# SNES-logo-leds.net
KiCad netlist of a schematic drawn in EAGLE
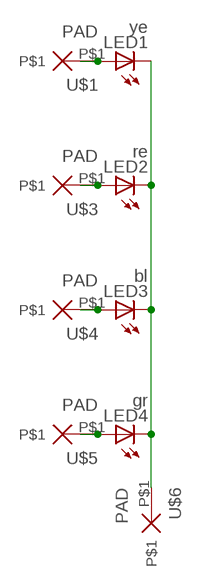
[diagram p0: schematic, sheet 1]

(export (version "E")
  (design (tool "Eeschema 10.0.6"))
  (components
    (comp (ref "LED1")
      (value "ye")
      (footprint "eagle-import:SML0805")
      (libsource (lib "eagle-import") (part "LEDSML0805"))
    )
    (comp (ref "LED2")
      (value "re")
      (footprint "eagle-import:SML0805")
      (libsource (lib "eagle-import") (part "LEDSML0805"))
    )
    (comp (ref "LED3")
      (value "bl")
      (footprint "eagle-import:SML0805")
      (libsource (lib "eagle-import") (part "LEDSML0805"))
    )
    (comp (ref "LED4")
      (value "gr")
      (footprint "eagle-import:SML0805")
      (libsource (lib "eagle-import") (part "LEDSML0805"))
    )
    (comp (ref "U$1")
      (value "PAD")
      (footprint "eagle-import:PAD")
      (libsource (lib "eagle-import") (part "PAD"))
    )
    (comp (ref "U$3")
      (value "PAD")
      (footprint "eagle-import:PAD")
      (libsource (lib "eagle-import") (part "PAD"))
    )
    (comp (ref "U$4")
      (value "PAD")
      (footprint "eagle-import:PAD")
      (libsource (lib "eagle-import") (part "PAD"))
    )
    (comp (ref "U$5")
      (value "PAD")
      (footprint "eagle-import:PAD")
      (libsource (lib "eagle-import") (part "PAD"))
    )
    (comp (ref "U$6")
      (value "PAD")
      (footprint "eagle-import:PAD")
      (libsource (lib "eagle-import") (part "PAD"))
    )
  )
  (nets
    (net (code "1") (name "Net-(LED1-PadA)") (class "Default")
      (node (ref "LED1") (pin "A") (pinfunction "A_A") (pintype "passive"))
      (node (ref "U$1") (pin "P$1") (pinfunction "P$1_P$1") (pintype "bidirectional"))
    )
    (net (code "2") (name "Net-(LED1-PadC)") (class "Default")
      (node (ref "LED1") (pin "C") (pinfunction "C_C") (pintype "passive"))
      (node (ref "LED2") (pin "C") (pinfunction "C_C") (pintype "passive"))
      (node (ref "LED3") (pin "C") (pinfunction "C_C") (pintype "passive"))
      (node (ref "LED4") (pin "C") (pinfunction "C_C") (pintype "passive"))
      (node (ref "U$6") (pin "P$1") (pinfunction "P$1_P$1") (pintype "bidirectional"))
    )
    (net (code "3") (name "Net-(LED2-PadA)") (class "Default")
      (node (ref "LED2") (pin "A") (pinfunction "A_A") (pintype "passive"))
      (node (ref "U$3") (pin "P$1") (pinfunction "P$1_P$1") (pintype "bidirectional"))
    )
    (net (code "4") (name "Net-(LED3-PadA)") (class "Default")
      (node (ref "LED3") (pin "A") (pinfunction "A_A") (pintype "passive"))
      (node (ref "U$4") (pin "P$1") (pinfunction "P$1_P$1") (pintype "bidirectional"))
    )
    (net (code "5") (name "Net-(LED4-PadA)") (class "Default")
      (node (ref "LED4") (pin "A") (pinfunction "A_A") (pintype "passive"))
      (node (ref "U$5") (pin "P$1") (pinfunction "P$1_P$1") (pintype "bidirectional"))
    )
  )
)
